# Slave_NFC.net
KiCad netlist of a schematic drawn in EAGLE
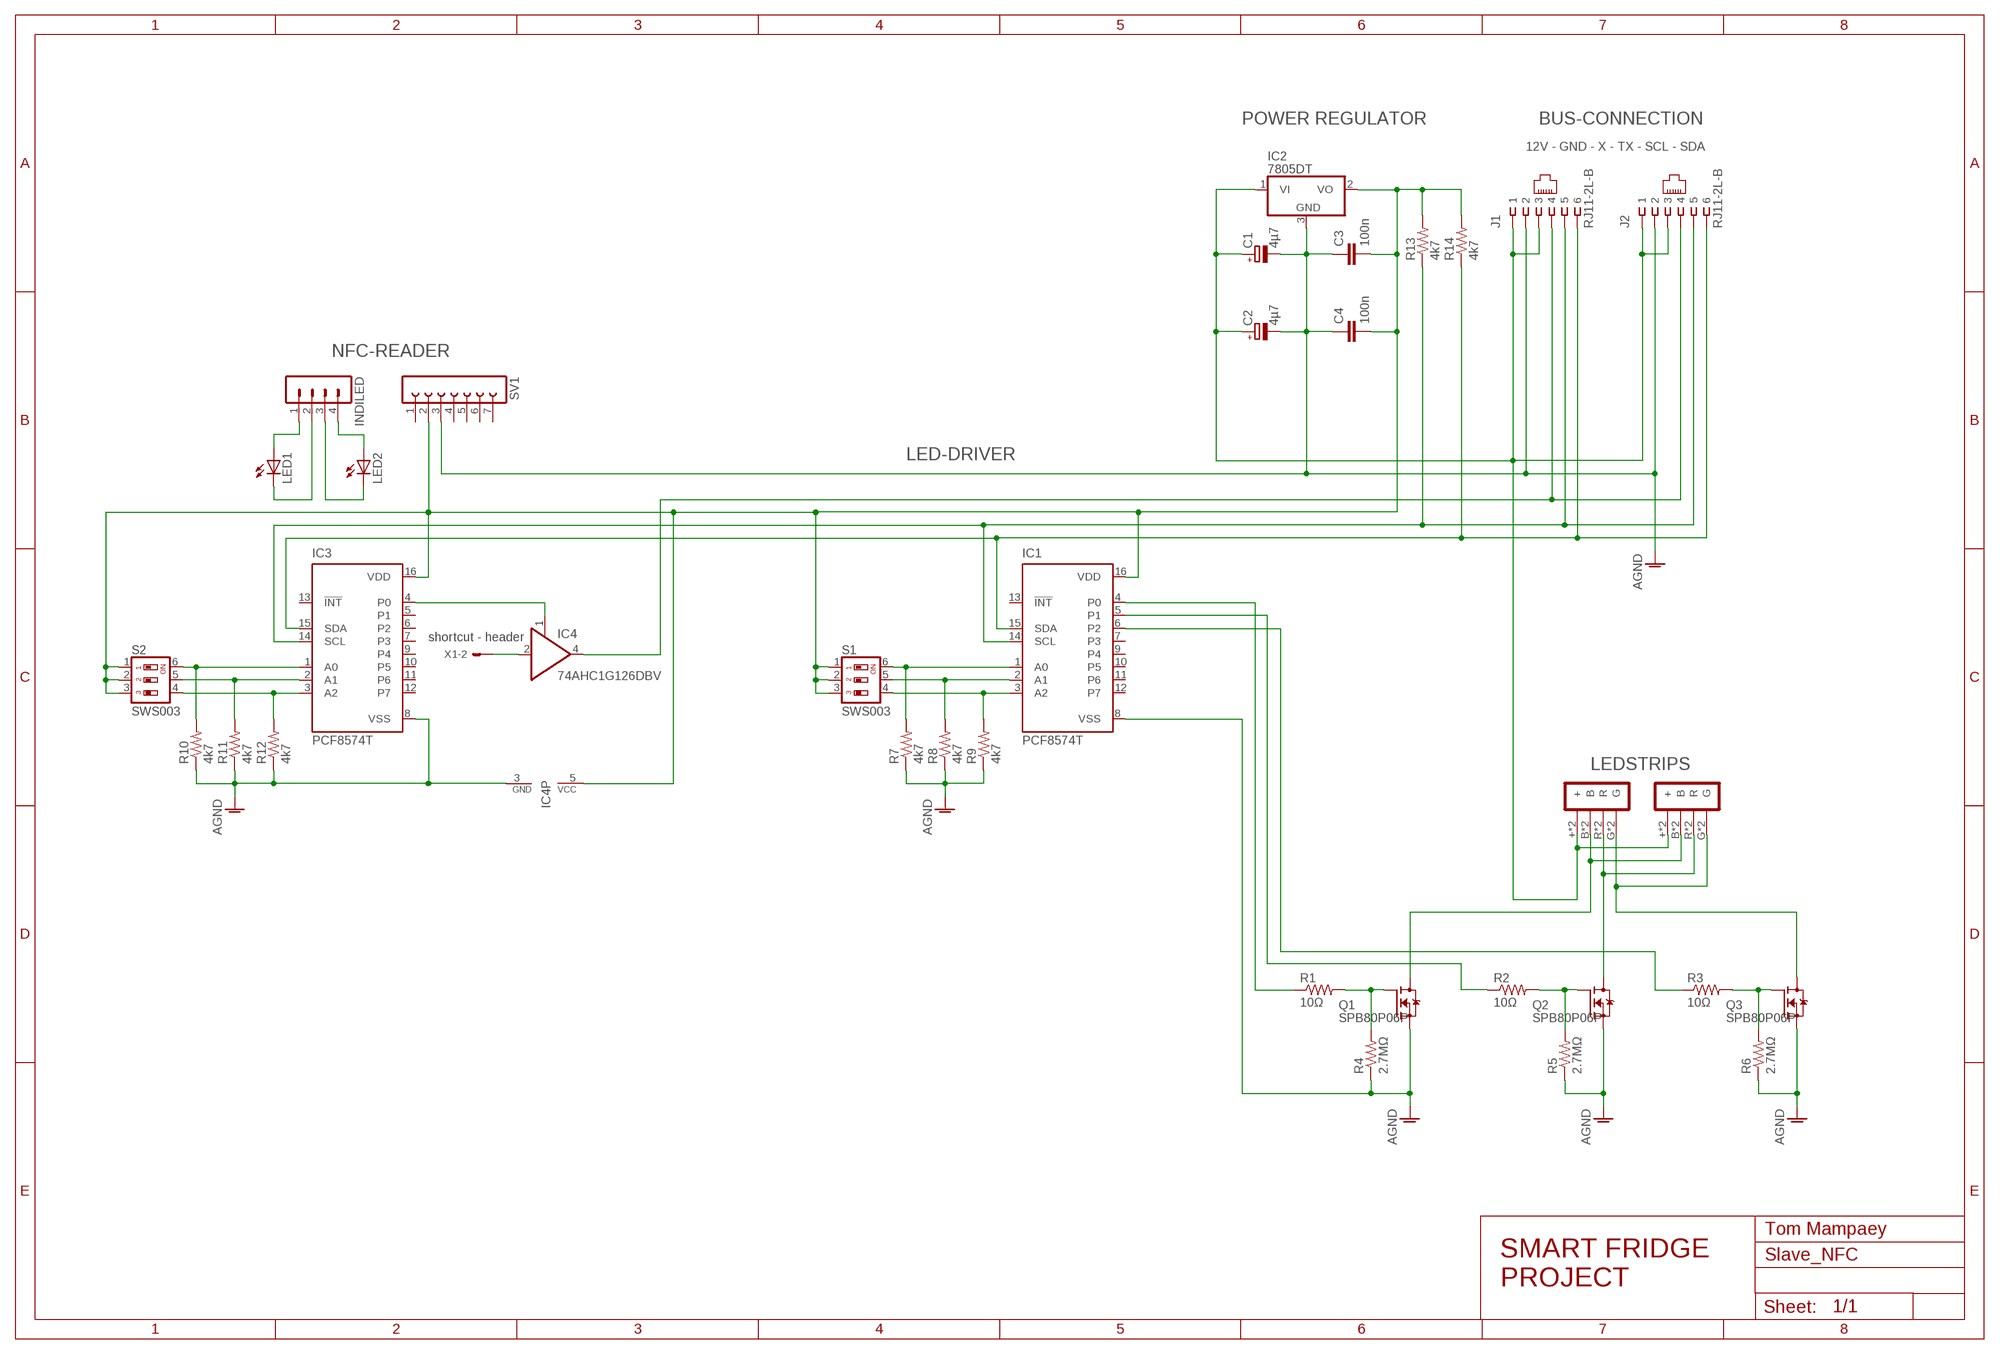
[diagram p0: schematic, sheet 1]

(export (version "E")
  (design (tool "Eeschema 10.0.6"))
  (components
    (comp (ref "C1")
      (value "4µ7")
      (footprint "eagle-import:PANASONIC_B")
      (libsource (lib "eagle-import") (part "CPOL-EUB"))
    )
    (comp (ref "C2")
      (value "4µ7")
      (footprint "eagle-import:PANASONIC_B")
      (libsource (lib "eagle-import") (part "CPOL-EUB"))
    )
    (comp (ref "C3")
      (value "100n")
      (footprint "eagle-import:C0603")
      (libsource (lib "eagle-import") (part "C-EUC0603"))
    )
    (comp (ref "C4")
      (value "100n")
      (footprint "eagle-import:C0603")
      (libsource (lib "eagle-import") (part "C-EUC0603"))
    )
    (comp (ref "IC1")
      (value "PCF8574T")
      (footprint "eagle-import:SO16W")
      (fields (field (name "MPN") "PCF8574T/3,512"))
      (libsource (lib "eagle-import") (part "PCF8574T"))
    )
    (comp (ref "IC2")
      (value "7805DT")
      (footprint "eagle-import:TO252")
      (libsource (lib "eagle-import") (part "78DT05"))
    )
    (comp (ref "IC3")
      (value "PCF8574T")
      (footprint "eagle-import:SO16W")
      (fields (field (name "MPN") "PCF8574T/3,512"))
      (libsource (lib "eagle-import") (part "PCF8574T"))
    )
    (comp (ref "IC4")
      (value "74AHC1G126DBV")
      (footprint "eagle-import:SOT23-5")
      (libsource (lib "eagle-import") (part "741G126DBVAHC"))
    )
    (comp (ref "INDILED")
      (value "MA04-1")
      (footprint "eagle-import:MA04-1")
      (fields (field (name "OC_FARNELL") "unknown") (field (name "OC_NEWARK") "unknown"))
      (libsource (lib "eagle-import") (part "MA04-1"))
    )
    (comp (ref "J1")
      (value "RJ11-2L-B")
      (footprint "eagle-import:RJ11-NO_SHIELD")
      (fields (field (name "MF") "TYCO ELECTRONICS"))
      (libsource (lib "eagle-import") (part "RJ11-2L-B"))
    )
    (comp (ref "J2")
      (value "RJ11-2L-B")
      (footprint "eagle-import:RJ11-NO_SHIELD")
      (fields (field (name "MF") "TYCO ELECTRONICS"))
      (libsource (lib "eagle-import") (part "RJ11-2L-B"))
    )
    (comp (ref "LED1")
      (value "LEDB152")
      (footprint "eagle-import:Q62902-B152")
      (libsource (lib "eagle-import") (part "LEDB152"))
    )
    (comp (ref "LED2")
      (value "LEDB152")
      (footprint "eagle-import:Q62902-B152")
      (libsource (lib "eagle-import") (part "LEDB152"))
    )
    (comp (ref "Q1")
      (value "SPB80P06P")
      (footprint "eagle-import:TO263")
      (libsource (lib "eagle-import") (part "SPB80P06P"))
    )
    (comp (ref "Q2")
      (value "SPB80P06P")
      (footprint "eagle-import:TO263")
      (libsource (lib "eagle-import") (part "SPB80P06P"))
    )
    (comp (ref "Q3")
      (value "SPB80P06P")
      (footprint "eagle-import:TO263")
      (libsource (lib "eagle-import") (part "SPB80P06P"))
    )
    (comp (ref "R1")
      (value "10Ω")
      (footprint "eagle-import:R0402")
      (libsource (lib "eagle-import") (part "R-US_R0402"))
    )
    (comp (ref "R2")
      (value "10Ω")
      (footprint "eagle-import:R0402")
      (libsource (lib "eagle-import") (part "R-US_R0402"))
    )
    (comp (ref "R3")
      (value "10Ω")
      (footprint "eagle-import:R0402")
      (libsource (lib "eagle-import") (part "R-US_R0402"))
    )
    (comp (ref "R4")
      (value "2.7MΩ")
      (footprint "eagle-import:R0402")
      (libsource (lib "eagle-import") (part "R-US_R0402"))
    )
    (comp (ref "R5")
      (value "2.7MΩ")
      (footprint "eagle-import:R0402")
      (libsource (lib "eagle-import") (part "R-US_R0402"))
    )
    (comp (ref "R6")
      (value "2.7MΩ")
      (footprint "eagle-import:R0402")
      (libsource (lib "eagle-import") (part "R-US_R0402"))
    )
    (comp (ref "R7")
      (value "4k7")
      (footprint "eagle-import:R0402")
      (libsource (lib "eagle-import") (part "R-US_R0402"))
    )
    (comp (ref "R8")
      (value "4k7")
      (footprint "eagle-import:R0402")
      (libsource (lib "eagle-import") (part "R-US_R0402"))
    )
    (comp (ref "R9")
      (value "4k7")
      (footprint "eagle-import:R0402")
      (libsource (lib "eagle-import") (part "R-US_R0402"))
    )
    (comp (ref "R10")
      (value "4k7")
      (footprint "eagle-import:R0402")
      (libsource (lib "eagle-import") (part "R-US_R0402"))
    )
    (comp (ref "R11")
      (value "4k7")
      (footprint "eagle-import:R0402")
      (libsource (lib "eagle-import") (part "R-US_R0402"))
    )
    (comp (ref "R12")
      (value "4k7")
      (footprint "eagle-import:R0402")
      (libsource (lib "eagle-import") (part "R-US_R0402"))
    )
    (comp (ref "R13")
      (value "4k7")
      (footprint "eagle-import:R0402")
      (libsource (lib "eagle-import") (part "R-US_R0402"))
    )
    (comp (ref "R14")
      (value "4k7")
      (footprint "eagle-import:R0402")
      (libsource (lib "eagle-import") (part "R-US_R0402"))
    )
    (comp (ref "S1")
      (value "SWS003")
      (footprint "eagle-import:SMS-003")
      (libsource (lib "eagle-import") (part "SWS003"))
    )
    (comp (ref "S2")
      (value "SWS003")
      (footprint "eagle-import:SMS-003")
      (libsource (lib "eagle-import") (part "SWS003"))
    )
    (comp (ref "SV1")
      (value "FE07-1")
      (footprint "eagle-import:FE07")
      (libsource (lib "eagle-import") (part "FE07-1"))
    )
    (comp (ref "U$1")
      (value "LED_S")
      (footprint "eagle-import:LED_P")
      (libsource (lib "eagle-import") (part "LED_S"))
    )
    (comp (ref "U$2")
      (value "LED_S")
      (footprint "eagle-import:LED_P")
      (libsource (lib "eagle-import") (part "LED_S"))
    )
    (comp (ref "X1")
      (value "22-23-2101")
      (footprint "eagle-import:22-23-2101")
      (fields
        (field (name "MF") "MOLEX")
        (field (name "MPN") "22-23-2101")
        (field (name "OC_FARNELL") "1756828")
        (field (name "OC_NEWARK") "94C0765")
      )
      (libsource (lib "eagle-import") (part "22-23-2101"))
    )
  )
  (nets
    (net (code "1") (name "AGND") (class "Default")
      (node (ref "C1") (pin "-") (pinfunction "-_-") (pintype "passive"))
      (node (ref "C2") (pin "-") (pinfunction "-_-") (pintype "passive"))
      (node (ref "C3") (pin "1") (pinfunction "1_1") (pintype "passive"))
      (node (ref "C4") (pin "1") (pinfunction "1_1") (pintype "passive"))
      (node (ref "IC1") (pin "8") (pinfunction "VSS_8") (pintype "power_in"))
      (node (ref "IC2") (pin "3") (pinfunction "GND_3") (pintype "passive"))
      (node (ref "IC3") (pin "8") (pinfunction "VSS_8") (pintype "power_in"))
      (node (ref "IC4") (pin "3") (pinfunction "GND_3") (pintype "power_in"))
      (node (ref "J1") (pin "2") (pinfunction "2_2") (pintype "passive"))
      (node (ref "J2") (pin "2") (pinfunction "2_2") (pintype "passive"))
      (node (ref "Q1") (pin "2") (pinfunction "D_2") (pintype "passive"))
      (node (ref "Q2") (pin "2") (pinfunction "D_2") (pintype "passive"))
      (node (ref "Q3") (pin "2") (pinfunction "D_2") (pintype "passive"))
      (node (ref "R10") (pin "1") (pinfunction "1_1") (pintype "passive"))
      (node (ref "R11") (pin "1") (pinfunction "1_1") (pintype "passive"))
      (node (ref "R12") (pin "1") (pinfunction "1_1") (pintype "passive"))
      (node (ref "R4") (pin "1") (pinfunction "1_1") (pintype "passive"))
      (node (ref "R5") (pin "1") (pinfunction "1_1") (pintype "passive"))
      (node (ref "R6") (pin "1") (pinfunction "1_1") (pintype "passive"))
      (node (ref "R7") (pin "1") (pinfunction "1_1") (pintype "passive"))
      (node (ref "R8") (pin "1") (pinfunction "1_1") (pintype "passive"))
      (node (ref "R9") (pin "1") (pinfunction "1_1") (pintype "passive"))
      (node (ref "SV1") (pin "3") (pinfunction "3_3") (pintype "passive"))
    )
    (net (code "2") (name "Net-(IC1-A0)") (class "Default")
      (node (ref "IC1") (pin "1") (pinfunction "A0_1") (pintype "input"))
      (node (ref "R7") (pin "2") (pinfunction "2_2") (pintype "passive"))
      (node (ref "S1") (pin "6") (pinfunction "6_6") (pintype "passive"))
    )
    (net (code "3") (name "Net-(IC1-A1)") (class "Default")
      (node (ref "IC1") (pin "2") (pinfunction "A1_2") (pintype "input"))
      (node (ref "R8") (pin "2") (pinfunction "2_2") (pintype "passive"))
      (node (ref "S1") (pin "5") (pinfunction "5_5") (pintype "passive"))
    )
    (net (code "4") (name "Net-(IC1-A2)") (class "Default")
      (node (ref "IC1") (pin "3") (pinfunction "A2_3") (pintype "input"))
      (node (ref "R9") (pin "2") (pinfunction "2_2") (pintype "passive"))
      (node (ref "S1") (pin "4") (pinfunction "4_4") (pintype "passive"))
    )
    (net (code "5") (name "Net-(IC1-P0)") (class "Default")
      (node (ref "IC1") (pin "4") (pinfunction "P0_4") (pintype "bidirectional"))
      (node (ref "R1") (pin "1") (pinfunction "1_1") (pintype "passive"))
    )
    (net (code "6") (name "Net-(IC1-P1)") (class "Default")
      (node (ref "IC1") (pin "5") (pinfunction "P1_5") (pintype "bidirectional"))
      (node (ref "R2") (pin "1") (pinfunction "1_1") (pintype "passive"))
    )
    (net (code "7") (name "Net-(IC1-P2)") (class "Default")
      (node (ref "IC1") (pin "6") (pinfunction "P2_6") (pintype "bidirectional"))
      (node (ref "R3") (pin "1") (pinfunction "1_1") (pintype "passive"))
    )
    (net (code "8") (name "Net-(IC1-SCL)") (class "Default")
      (node (ref "IC1") (pin "14") (pinfunction "SCL_14") (pintype "input"))
      (node (ref "IC3") (pin "14") (pinfunction "SCL_14") (pintype "input"))
      (node (ref "J1") (pin "5") (pinfunction "5_5") (pintype "passive"))
      (node (ref "J2") (pin "5") (pinfunction "5_5") (pintype "passive"))
      (node (ref "R13") (pin "1") (pinfunction "1_1") (pintype "passive"))
    )
    (net (code "9") (name "Net-(IC1-SDA)") (class "Default")
      (node (ref "IC1") (pin "15") (pinfunction "SDA_15") (pintype "bidirectional"))
      (node (ref "IC3") (pin "15") (pinfunction "SDA_15") (pintype "bidirectional"))
      (node (ref "J1") (pin "6") (pinfunction "6_6") (pintype "passive"))
      (node (ref "J2") (pin "6") (pinfunction "6_6") (pintype "passive"))
      (node (ref "R14") (pin "1") (pinfunction "1_1") (pintype "passive"))
    )
    (net (code "10") (name "Net-(IC1-VDD)") (class "Default")
      (node (ref "C3") (pin "2") (pinfunction "2_2") (pintype "passive"))
      (node (ref "C4") (pin "2") (pinfunction "2_2") (pintype "passive"))
      (node (ref "IC1") (pin "16") (pinfunction "VDD_16") (pintype "power_in"))
      (node (ref "IC2") (pin "2") (pinfunction "VO_2") (pintype "passive"))
      (node (ref "IC3") (pin "16") (pinfunction "VDD_16") (pintype "power_in"))
      (node (ref "IC4") (pin "5") (pinfunction "VCC_5") (pintype "power_in"))
      (node (ref "R13") (pin "2") (pinfunction "2_2") (pintype "passive"))
      (node (ref "R14") (pin "2") (pinfunction "2_2") (pintype "passive"))
      (node (ref "S1") (pin "1") (pinfunction "1_1") (pintype "passive"))
      (node (ref "S1") (pin "2") (pinfunction "2_2") (pintype "passive"))
      (node (ref "S1") (pin "3") (pinfunction "3_3") (pintype "passive"))
      (node (ref "S2") (pin "1") (pinfunction "1_1") (pintype "passive"))
      (node (ref "S2") (pin "2") (pinfunction "2_2") (pintype "passive"))
      (node (ref "S2") (pin "3") (pinfunction "3_3") (pintype "passive"))
      (node (ref "SV1") (pin "2") (pinfunction "2_2") (pintype "passive"))
    )
    (net (code "11") (name "Net-(IC2-VI)") (class "Default")
      (node (ref "C1") (pin "+") (pinfunction "+_+") (pintype "passive"))
      (node (ref "C2") (pin "+") (pinfunction "+_+") (pintype "passive"))
      (node (ref "IC2") (pin "1") (pinfunction "VI_1") (pintype "input"))
      (node (ref "J1") (pin "1") (pinfunction "1_1") (pintype "passive"))
      (node (ref "J1") (pin "3") (pinfunction "3_3") (pintype "passive"))
      (node (ref "J2") (pin "1") (pinfunction "1_1") (pintype "passive"))
      (node (ref "J2") (pin "3") (pinfunction "3_3") (pintype "passive"))
      (node (ref "U$1") (pin "+") (pinfunction "+_+") (pintype "input"))
      (node (ref "U$1") (pin "+1") (pinfunction "+_+1") (pintype "input"))
      (node (ref "U$2") (pin "+") (pinfunction "+_+") (pintype "input"))
      (node (ref "U$2") (pin "+1") (pinfunction "+_+1") (pintype "input"))
    )
    (net (code "12") (name "Net-(IC3-A0)") (class "Default")
      (node (ref "IC3") (pin "1") (pinfunction "A0_1") (pintype "input"))
      (node (ref "R10") (pin "2") (pinfunction "2_2") (pintype "passive"))
      (node (ref "S2") (pin "6") (pinfunction "6_6") (pintype "passive"))
    )
    (net (code "13") (name "Net-(IC3-A1)") (class "Default")
      (node (ref "IC3") (pin "2") (pinfunction "A1_2") (pintype "input"))
      (node (ref "R11") (pin "2") (pinfunction "2_2") (pintype "passive"))
      (node (ref "S2") (pin "5") (pinfunction "5_5") (pintype "passive"))
    )
    (net (code "14") (name "Net-(IC3-A2)") (class "Default")
      (node (ref "IC3") (pin "3") (pinfunction "A2_3") (pintype "input"))
      (node (ref "R12") (pin "2") (pinfunction "2_2") (pintype "passive"))
      (node (ref "S2") (pin "4") (pinfunction "4_4") (pintype "passive"))
    )
    (net (code "15") (name "Net-(IC3-P0)") (class "Default")
      (node (ref "IC3") (pin "4") (pinfunction "P0_4") (pintype "bidirectional"))
      (node (ref "IC4") (pin "1") (pinfunction "OE_1") (pintype "input"))
    )
    (net (code "16") (name "Net-(IC4A-I)") (class "Default")
      (node (ref "IC4") (pin "2") (pinfunction "I_2") (pintype "input"))
      (node (ref "X1") (pin "2") (pinfunction "S_2") (pintype "passive"))
    )
    (net (code "17") (name "Net-(IC4A-O)") (class "Default")
      (node (ref "IC4") (pin "4") (pinfunction "O_4") (pintype "output"))
      (node (ref "J1") (pin "4") (pinfunction "4_4") (pintype "passive"))
      (node (ref "J2") (pin "4") (pinfunction "4_4") (pintype "passive"))
    )
    (net (code "18") (name "Net-(INDILED-Pad1)") (class "Default")
      (node (ref "INDILED") (pin "1") (pinfunction "1_1") (pintype "passive"))
      (node (ref "LED1") (pin "A") (pinfunction "A_A") (pintype "passive"))
    )
    (net (code "19") (name "Net-(INDILED-Pad4)") (class "Default")
      (node (ref "INDILED") (pin "4") (pinfunction "4_4") (pintype "passive"))
      (node (ref "LED2") (pin "A") (pinfunction "A_A") (pintype "passive"))
    )
    (net (code "20") (name "Net-(LED1-C)") (class "Default")
      (node (ref "INDILED") (pin "2") (pinfunction "2_2") (pintype "passive"))
      (node (ref "LED1") (pin "K") (pinfunction "C_K") (pintype "passive"))
    )
    (net (code "21") (name "Net-(LED2-C)") (class "Default")
      (node (ref "INDILED") (pin "3") (pinfunction "3_3") (pintype "passive"))
      (node (ref "LED2") (pin "K") (pinfunction "C_K") (pintype "passive"))
    )
    (net (code "22") (name "Net-(Q1-G)") (class "Default")
      (node (ref "Q1") (pin "1") (pinfunction "G_1") (pintype "passive"))
      (node (ref "R1") (pin "2") (pinfunction "2_2") (pintype "passive"))
      (node (ref "R4") (pin "2") (pinfunction "2_2") (pintype "passive"))
    )
    (net (code "23") (name "Net-(Q1-S)") (class "Default")
      (node (ref "Q1") (pin "3") (pinfunction "S_3") (pintype "passive"))
      (node (ref "U$1") (pin "B") (pinfunction "B_B") (pintype "input"))
      (node (ref "U$1") (pin "B1") (pinfunction "B_B1") (pintype "input"))
      (node (ref "U$2") (pin "B") (pinfunction "B_B") (pintype "input"))
      (node (ref "U$2") (pin "B1") (pinfunction "B_B1") (pintype "input"))
    )
    (net (code "24") (name "Net-(Q2-G)") (class "Default")
      (node (ref "Q2") (pin "1") (pinfunction "G_1") (pintype "passive"))
      (node (ref "R2") (pin "2") (pinfunction "2_2") (pintype "passive"))
      (node (ref "R5") (pin "2") (pinfunction "2_2") (pintype "passive"))
    )
    (net (code "25") (name "Net-(Q2-S)") (class "Default")
      (node (ref "Q2") (pin "3") (pinfunction "S_3") (pintype "passive"))
      (node (ref "U$1") (pin "R") (pinfunction "R_R") (pintype "input"))
      (node (ref "U$1") (pin "R1") (pinfunction "R_R1") (pintype "input"))
      (node (ref "U$2") (pin "R") (pinfunction "R_R") (pintype "input"))
      (node (ref "U$2") (pin "R1") (pinfunction "R_R1") (pintype "input"))
    )
    (net (code "26") (name "Net-(Q3-G)") (class "Default")
      (node (ref "Q3") (pin "1") (pinfunction "G_1") (pintype "passive"))
      (node (ref "R3") (pin "2") (pinfunction "2_2") (pintype "passive"))
      (node (ref "R6") (pin "2") (pinfunction "2_2") (pintype "passive"))
    )
    (net (code "27") (name "Net-(Q3-S)") (class "Default")
      (node (ref "Q3") (pin "3") (pinfunction "S_3") (pintype "passive"))
      (node (ref "U$1") (pin "G") (pinfunction "G_G") (pintype "input"))
      (node (ref "U$1") (pin "G1") (pinfunction "G_G1") (pintype "input"))
      (node (ref "U$2") (pin "G") (pinfunction "G_G") (pintype "input"))
      (node (ref "U$2") (pin "G1") (pinfunction "G_G1") (pintype "input"))
    )
    (net (code "28") (name "unconnected-(IC1-P3-Pad7)") (class "Default")
      (node (ref "IC1") (pin "7") (pinfunction "P3_7") (pintype "bidirectional"))
    )
    (net (code "29") (name "unconnected-(IC1-P4-Pad9)") (class "Default")
      (node (ref "IC1") (pin "9") (pinfunction "P4_9") (pintype "bidirectional"))
    )
    (net (code "30") (name "unconnected-(IC1-P5-Pad10)") (class "Default")
      (node (ref "IC1") (pin "10") (pinfunction "P5_10") (pintype "bidirectional"))
    )
    (net (code "31") (name "unconnected-(IC1-P6-Pad11)") (class "Default")
      (node (ref "IC1") (pin "11") (pinfunction "P6_11") (pintype "bidirectional"))
    )
    (net (code "32") (name "unconnected-(IC1-P7-Pad12)") (class "Default")
      (node (ref "IC1") (pin "12") (pinfunction "P7_12") (pintype "bidirectional"))
    )
    (net (code "33") (name "unconnected-(IC1-~{INT}-Pad13)") (class "Default")
      (node (ref "IC1") (pin "13") (pinfunction "~{INT}_13") (pintype "output"))
    )
    (net (code "34") (name "unconnected-(IC3-P1-Pad5)") (class "Default")
      (node (ref "IC3") (pin "5") (pinfunction "P1_5") (pintype "bidirectional"))
    )
    (net (code "35") (name "unconnected-(IC3-P2-Pad6)") (class "Default")
      (node (ref "IC3") (pin "6") (pinfunction "P2_6") (pintype "bidirectional"))
    )
    (net (code "36") (name "unconnected-(IC3-P3-Pad7)") (class "Default")
      (node (ref "IC3") (pin "7") (pinfunction "P3_7") (pintype "bidirectional"))
    )
    (net (code "37") (name "unconnected-(IC3-P4-Pad9)") (class "Default")
      (node (ref "IC3") (pin "9") (pinfunction "P4_9") (pintype "bidirectional"))
    )
    (net (code "38") (name "unconnected-(IC3-P5-Pad10)") (class "Default")
      (node (ref "IC3") (pin "10") (pinfunction "P5_10") (pintype "bidirectional"))
    )
    (net (code "39") (name "unconnected-(IC3-P6-Pad11)") (class "Default")
      (node (ref "IC3") (pin "11") (pinfunction "P6_11") (pintype "bidirectional"))
    )
    (net (code "40") (name "unconnected-(IC3-P7-Pad12)") (class "Default")
      (node (ref "IC3") (pin "12") (pinfunction "P7_12") (pintype "bidirectional"))
    )
    (net (code "41") (name "unconnected-(IC3-~{INT}-Pad13)") (class "Default")
      (node (ref "IC3") (pin "13") (pinfunction "~{INT}_13") (pintype "output"))
    )
    (net (code "42") (name "unconnected-(SV1-Pad1)") (class "Default")
      (node (ref "SV1") (pin "1") (pinfunction "1_1") (pintype "passive"))
    )
    (net (code "43") (name "unconnected-(SV1-Pad4)") (class "Default")
      (node (ref "SV1") (pin "4") (pinfunction "4_4") (pintype "passive"))
    )
    (net (code "44") (name "unconnected-(SV1-Pad5)") (class "Default")
      (node (ref "SV1") (pin "5") (pinfunction "5_5") (pintype "passive"))
    )
    (net (code "45") (name "unconnected-(SV1-Pad6)") (class "Default")
      (node (ref "SV1") (pin "6") (pinfunction "6_6") (pintype "passive"))
    )
    (net (code "46") (name "unconnected-(SV1-Pad7)") (class "Default")
      (node (ref "SV1") (pin "7") (pinfunction "7_7") (pintype "passive"))
    )
  )
)
